# m4_debug.net
KiCad netlist of a schematic drawn in Altium Designer
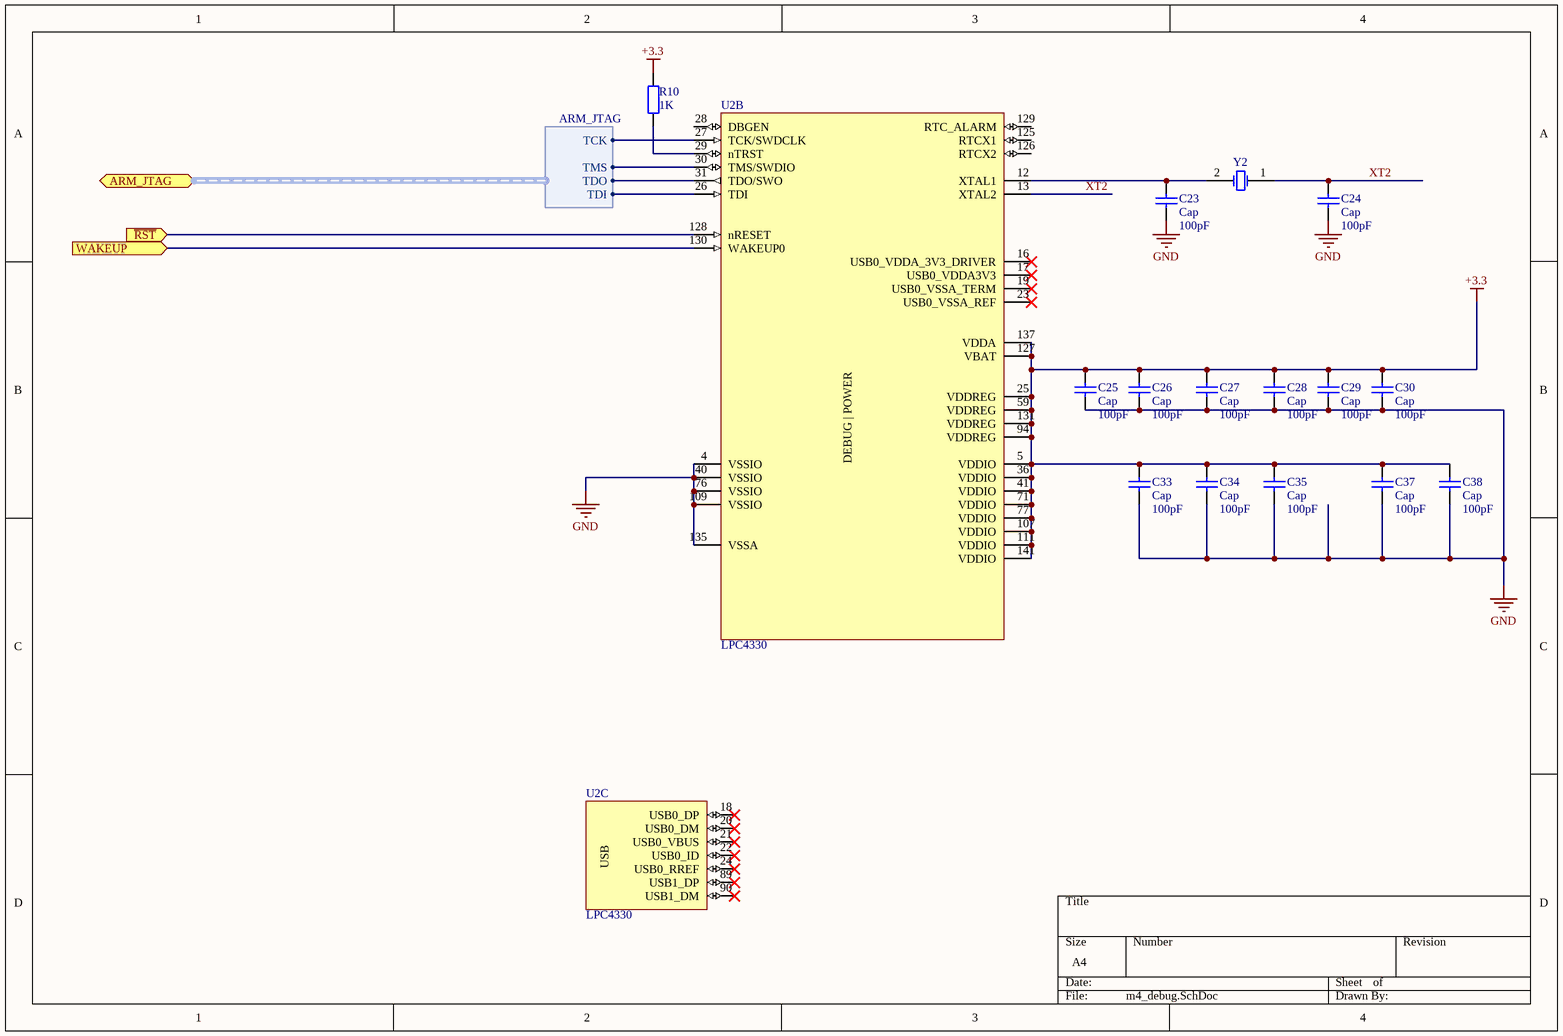
[diagram p0: m4_debug.SchDoc]

(export (version "E")
  (design (tool "Eeschema 10.0.6"))
  (components
    (comp (ref "C23")
      (value "Cap")
      (footprint "C0603")
      (description "Capacitor")
      (fields (field (name "ALTIUM_VALUE") "100pF") (field (name "PUBLISHER") "Altium Limited"))
      (libsource (lib "Miscellaneous Devices") (part "Cap"))
    )
    (comp (ref "C24")
      (value "Cap")
      (footprint "C0603")
      (description "Capacitor")
      (fields (field (name "ALTIUM_VALUE") "100pF") (field (name "PUBLISHER") "Altium Limited"))
      (libsource (lib "Miscellaneous Devices") (part "Cap"))
    )
    (comp (ref "C25")
      (value "Cap")
      (footprint "C0603")
      (description "Capacitor")
      (fields (field (name "ALTIUM_VALUE") "100pF") (field (name "PUBLISHER") "Altium Limited"))
      (libsource (lib "Miscellaneous Devices") (part "Cap"))
    )
    (comp (ref "C26")
      (value "Cap")
      (footprint "C0603")
      (description "Capacitor")
      (fields (field (name "ALTIUM_VALUE") "100pF") (field (name "PUBLISHER") "Altium Limited"))
      (libsource (lib "Miscellaneous Devices") (part "Cap"))
    )
    (comp (ref "C27")
      (value "Cap")
      (footprint "C0603")
      (description "Capacitor")
      (fields (field (name "ALTIUM_VALUE") "100pF") (field (name "PUBLISHER") "Altium Limited"))
      (libsource (lib "Miscellaneous Devices") (part "Cap"))
    )
    (comp (ref "C28")
      (value "Cap")
      (footprint "C0603")
      (description "Capacitor")
      (fields (field (name "ALTIUM_VALUE") "100pF") (field (name "PUBLISHER") "Altium Limited"))
      (libsource (lib "Miscellaneous Devices") (part "Cap"))
    )
    (comp (ref "C29")
      (value "Cap")
      (footprint "C0603")
      (description "Capacitor")
      (fields (field (name "ALTIUM_VALUE") "100pF") (field (name "PUBLISHER") "Altium Limited"))
      (libsource (lib "Miscellaneous Devices") (part "Cap"))
    )
    (comp (ref "C30")
      (value "Cap")
      (footprint "C0603")
      (description "Capacitor")
      (fields (field (name "ALTIUM_VALUE") "100pF") (field (name "PUBLISHER") "Altium Limited"))
      (libsource (lib "Miscellaneous Devices") (part "Cap"))
    )
    (comp (ref "C33")
      (value "Cap")
      (footprint "C0603")
      (description "Capacitor")
      (fields (field (name "ALTIUM_VALUE") "100pF") (field (name "PUBLISHER") "Altium Limited"))
      (libsource (lib "Miscellaneous Devices") (part "Cap"))
    )
    (comp (ref "C34")
      (value "Cap")
      (footprint "C0603")
      (description "Capacitor")
      (fields (field (name "ALTIUM_VALUE") "100pF") (field (name "PUBLISHER") "Altium Limited"))
      (libsource (lib "Miscellaneous Devices") (part "Cap"))
    )
    (comp (ref "C35")
      (value "Cap")
      (footprint "C0603")
      (description "Capacitor")
      (fields (field (name "ALTIUM_VALUE") "100pF") (field (name "PUBLISHER") "Altium Limited"))
      (libsource (lib "Miscellaneous Devices") (part "Cap"))
    )
    (comp (ref "C37")
      (value "Cap")
      (footprint "C0603")
      (description "Capacitor")
      (fields (field (name "ALTIUM_VALUE") "100pF") (field (name "PUBLISHER") "Altium Limited"))
      (libsource (lib "Miscellaneous Devices") (part "Cap"))
    )
    (comp (ref "C38")
      (value "Cap")
      (footprint "C0603")
      (description "Capacitor")
      (fields (field (name "ALTIUM_VALUE") "100pF") (field (name "PUBLISHER") "Altium Limited"))
      (libsource (lib "Miscellaneous Devices") (part "Cap"))
    )
    (comp (ref "R10")
      (value "1K")
      (footprint "R0603")
      (description "Resistor")
      (fields (field (name "Comment") "Res2") (field (name "PUBLISHER") "Altium Limited"))
      (libsource (lib "Miscellaneous Devices") (part "Res2"))
    )
    (comp (ref "U2")
      (value "LPC4330")
      (footprint "TSQFP50P2200X2200X160-144N")
      (description "MCU, 32BIT, ARM CORTEX M4&M0, 144LQFP")
      (libsource (lib "LPC4330") (part "LPC4330"))
    )
    (comp (ref "Y2")
      (value "XTAL")
      (footprint "C3E-24.000-12-3030-X")
      (description "Crystal Oscillator")
      (fields (field (name "PUBLISHER") "Altium Limited"))
      (libsource (lib "Miscellaneous Devices") (part "XTAL"))
    )
  )
  (nets
    (net (code "2") (name "+3.3") (class "Default")
      (node (ref "C25") (pin "1") (pinfunction "1_1") (pintype "passive"))
      (node (ref "C26") (pin "1") (pinfunction "1_1") (pintype "passive"))
      (node (ref "C27") (pin "1") (pinfunction "1_1") (pintype "passive"))
      (node (ref "C28") (pin "1") (pinfunction "1_1") (pintype "passive"))
      (node (ref "C29") (pin "1") (pinfunction "1_1") (pintype "passive"))
      (node (ref "C30") (pin "1") (pinfunction "1_1") (pintype "passive"))
      (node (ref "C33") (pin "1") (pinfunction "1_1") (pintype "passive"))
      (node (ref "C34") (pin "1") (pinfunction "1_1") (pintype "passive"))
      (node (ref "C35") (pin "1") (pinfunction "1_1") (pintype "passive"))
      (node (ref "C37") (pin "1") (pinfunction "1_1") (pintype "passive"))
      (node (ref "C38") (pin "1") (pinfunction "1_1") (pintype "passive"))
      (node (ref "R10") (pin "2") (pinfunction "2_2") (pintype "passive"))
      (node (ref "U2") (pin "107") (pinfunction "VDDIO_107") (pintype "power_in"))
      (node (ref "U2") (pin "111") (pinfunction "VDDIO_111") (pintype "power_in"))
      (node (ref "U2") (pin "127") (pinfunction "VBAT_127") (pintype "power_in"))
      (node (ref "U2") (pin "131") (pinfunction "VDDREG_131") (pintype "power_in"))
      (node (ref "U2") (pin "137") (pinfunction "VDDA_137") (pintype "power_in"))
      (node (ref "U2") (pin "141") (pinfunction "VDDIO_141") (pintype "power_in"))
      (node (ref "U2") (pin "25") (pinfunction "VDDREG_25") (pintype "power_in"))
      (node (ref "U2") (pin "36") (pinfunction "VDDIO_36") (pintype "power_in"))
      (node (ref "U2") (pin "41") (pinfunction "VDDIO_41") (pintype "power_in"))
      (node (ref "U2") (pin "5") (pinfunction "VDDIO_5") (pintype "power_in"))
      (node (ref "U2") (pin "59") (pinfunction "VDDREG_59") (pintype "power_in"))
      (node (ref "U2") (pin "71") (pinfunction "VDDIO_71") (pintype "power_in"))
      (node (ref "U2") (pin "77") (pinfunction "VDDIO_77") (pintype "power_in"))
      (node (ref "U2") (pin "94") (pinfunction "VDDREG_94") (pintype "power_in"))
    )
    (net (code "3") (name "/TCK") (class "Default")
      (node (ref "U2") (pin "27") (pinfunction "TCK/SWDCLK_27") (pintype "input"))
    )
    (net (code "4") (name "/TDI") (class "Default")
      (node (ref "U2") (pin "26") (pinfunction "TDI_26") (pintype "input"))
    )
    (net (code "5") (name "/TDO") (class "Default")
      (node (ref "U2") (pin "31") (pinfunction "TDO/SWO_31") (pintype "output"))
    )
    (net (code "6") (name "/TMS") (class "Default")
      (node (ref "U2") (pin "30") (pinfunction "TMS/SWDIO_30") (pintype "bidirectional"))
    )
    (net (code "7") (name "/WAKEUP") (class "Default")
      (node (ref "U2") (pin "130") (pinfunction "WAKEUP0_130") (pintype "input"))
    )
    (net (code "8") (name "/XT2") (class "Default")
      (node (ref "C24") (pin "2") (pinfunction "2_2") (pintype "passive"))
      (node (ref "U2") (pin "13") (pinfunction "XTAL2_13") (pintype "passive"))
      (node (ref "Y2") (pin "1") (pinfunction "OSC1_1") (pintype "passive"))
    )
    (net (code "10") (name "/~{RST}") (class "Default")
      (node (ref "U2") (pin "128") (pinfunction "nRESET_128") (pintype "input"))
    )
    (net (code "11") (name "GND") (class "Default")
      (node (ref "C23") (pin "1") (pinfunction "1_1") (pintype "passive"))
      (node (ref "C24") (pin "1") (pinfunction "1_1") (pintype "passive"))
      (node (ref "C25") (pin "2") (pinfunction "2_2") (pintype "passive"))
      (node (ref "C26") (pin "2") (pinfunction "2_2") (pintype "passive"))
      (node (ref "C27") (pin "2") (pinfunction "2_2") (pintype "passive"))
      (node (ref "C28") (pin "2") (pinfunction "2_2") (pintype "passive"))
      (node (ref "C29") (pin "2") (pinfunction "2_2") (pintype "passive"))
      (node (ref "C30") (pin "2") (pinfunction "2_2") (pintype "passive"))
      (node (ref "C33") (pin "2") (pinfunction "2_2") (pintype "passive"))
      (node (ref "C34") (pin "2") (pinfunction "2_2") (pintype "passive"))
      (node (ref "C35") (pin "2") (pinfunction "2_2") (pintype "passive"))
      (node (ref "C37") (pin "2") (pinfunction "2_2") (pintype "passive"))
      (node (ref "C38") (pin "2") (pinfunction "2_2") (pintype "passive"))
      (node (ref "U2") (pin "109") (pinfunction "VSSIO_109") (pintype "power_in"))
      (node (ref "U2") (pin "135") (pinfunction "VSSA_135") (pintype "power_in"))
      (node (ref "U2") (pin "4") (pinfunction "VSSIO_4") (pintype "power_in"))
      (node (ref "U2") (pin "40") (pinfunction "VSSIO_40") (pintype "power_in"))
      (node (ref "U2") (pin "76") (pinfunction "VSSIO_76") (pintype "power_in"))
    )
    (net (code "12") (name "Net-(U2B-XTAL1)") (class "Default")
      (node (ref "C23") (pin "2") (pinfunction "2_2") (pintype "passive"))
      (node (ref "U2") (pin "12") (pinfunction "XTAL1_12") (pintype "passive"))
      (node (ref "Y2") (pin "2") (pinfunction "OSC2_2") (pintype "passive"))
    )
    (net (code "13") (name "Net-(U2B-nTRST)") (class "Default")
      (node (ref "R10") (pin "1") (pinfunction "1_1") (pintype "passive"))
      (node (ref "U2") (pin "29") (pinfunction "nTRST_29") (pintype "bidirectional"))
    )
    (net (code "14") (name "unconnected-(U2B-DBGEN-Pad28)") (class "Default")
      (node (ref "U2") (pin "28") (pinfunction "DBGEN_28") (pintype "bidirectional"))
    )
    (net (code "15") (name "unconnected-(U2B-RTCX1-Pad125)") (class "Default")
      (node (ref "U2") (pin "125") (pinfunction "RTCX1_125") (pintype "bidirectional"))
    )
    (net (code "16") (name "unconnected-(U2B-RTCX2-Pad126)") (class "Default")
      (node (ref "U2") (pin "126") (pinfunction "RTCX2_126") (pintype "bidirectional"))
    )
    (net (code "17") (name "unconnected-(U2B-RTC_ALARM-Pad129)") (class "Default")
      (node (ref "U2") (pin "129") (pinfunction "RTC_ALARM_129") (pintype "bidirectional"))
    )
    (net (code "18") (name "unconnected-(U2B-USB0_VDDA3V3-Pad17)") (class "Default")
      (node (ref "U2") (pin "17") (pinfunction "USB0_VDDA3V3_17") (pintype "power_in+no_connect"))
    )
    (net (code "19") (name "unconnected-(U2B-USB0_VDDA_3V3_DRIVER-Pad16)") (class "Default")
      (node (ref "U2") (pin "16") (pinfunction "USB0_VDDA_3V3_DRIVER_16") (pintype "power_in+no_connect"))
    )
    (net (code "20") (name "unconnected-(U2B-USB0_VSSA_REF-Pad23)") (class "Default")
      (node (ref "U2") (pin "23") (pinfunction "USB0_VSSA_REF_23") (pintype "power_in+no_connect"))
    )
    (net (code "21") (name "unconnected-(U2B-USB0_VSSA_TERM-Pad19)") (class "Default")
      (node (ref "U2") (pin "19") (pinfunction "USB0_VSSA_TERM_19") (pintype "power_in+no_connect"))
    )
    (net (code "22") (name "unconnected-(U2C-USB0_DM-Pad20)") (class "Default")
      (node (ref "U2") (pin "20") (pinfunction "USB0_DM_20") (pintype "bidirectional+no_connect"))
    )
    (net (code "23") (name "unconnected-(U2C-USB0_DP-Pad18)") (class "Default")
      (node (ref "U2") (pin "18") (pinfunction "USB0_DP_18") (pintype "bidirectional+no_connect"))
    )
    (net (code "24") (name "unconnected-(U2C-USB0_ID-Pad22)") (class "Default")
      (node (ref "U2") (pin "22") (pinfunction "USB0_ID_22") (pintype "bidirectional+no_connect"))
    )
    (net (code "25") (name "unconnected-(U2C-USB0_RREF-Pad24)") (class "Default")
      (node (ref "U2") (pin "24") (pinfunction "USB0_RREF_24") (pintype "bidirectional+no_connect"))
    )
    (net (code "26") (name "unconnected-(U2C-USB0_VBUS-Pad21)") (class "Default")
      (node (ref "U2") (pin "21") (pinfunction "USB0_VBUS_21") (pintype "bidirectional+no_connect"))
    )
    (net (code "27") (name "unconnected-(U2C-USB1_DM-Pad90)") (class "Default")
      (node (ref "U2") (pin "90") (pinfunction "USB1_DM_90") (pintype "bidirectional+no_connect"))
    )
    (net (code "28") (name "unconnected-(U2C-USB1_DP-Pad89)") (class "Default")
      (node (ref "U2") (pin "89") (pinfunction "USB1_DP_89") (pintype "bidirectional+no_connect"))
    )
  )
)
